# 8051.net
KiCad netlist of a schematic drawn in Altium Designer
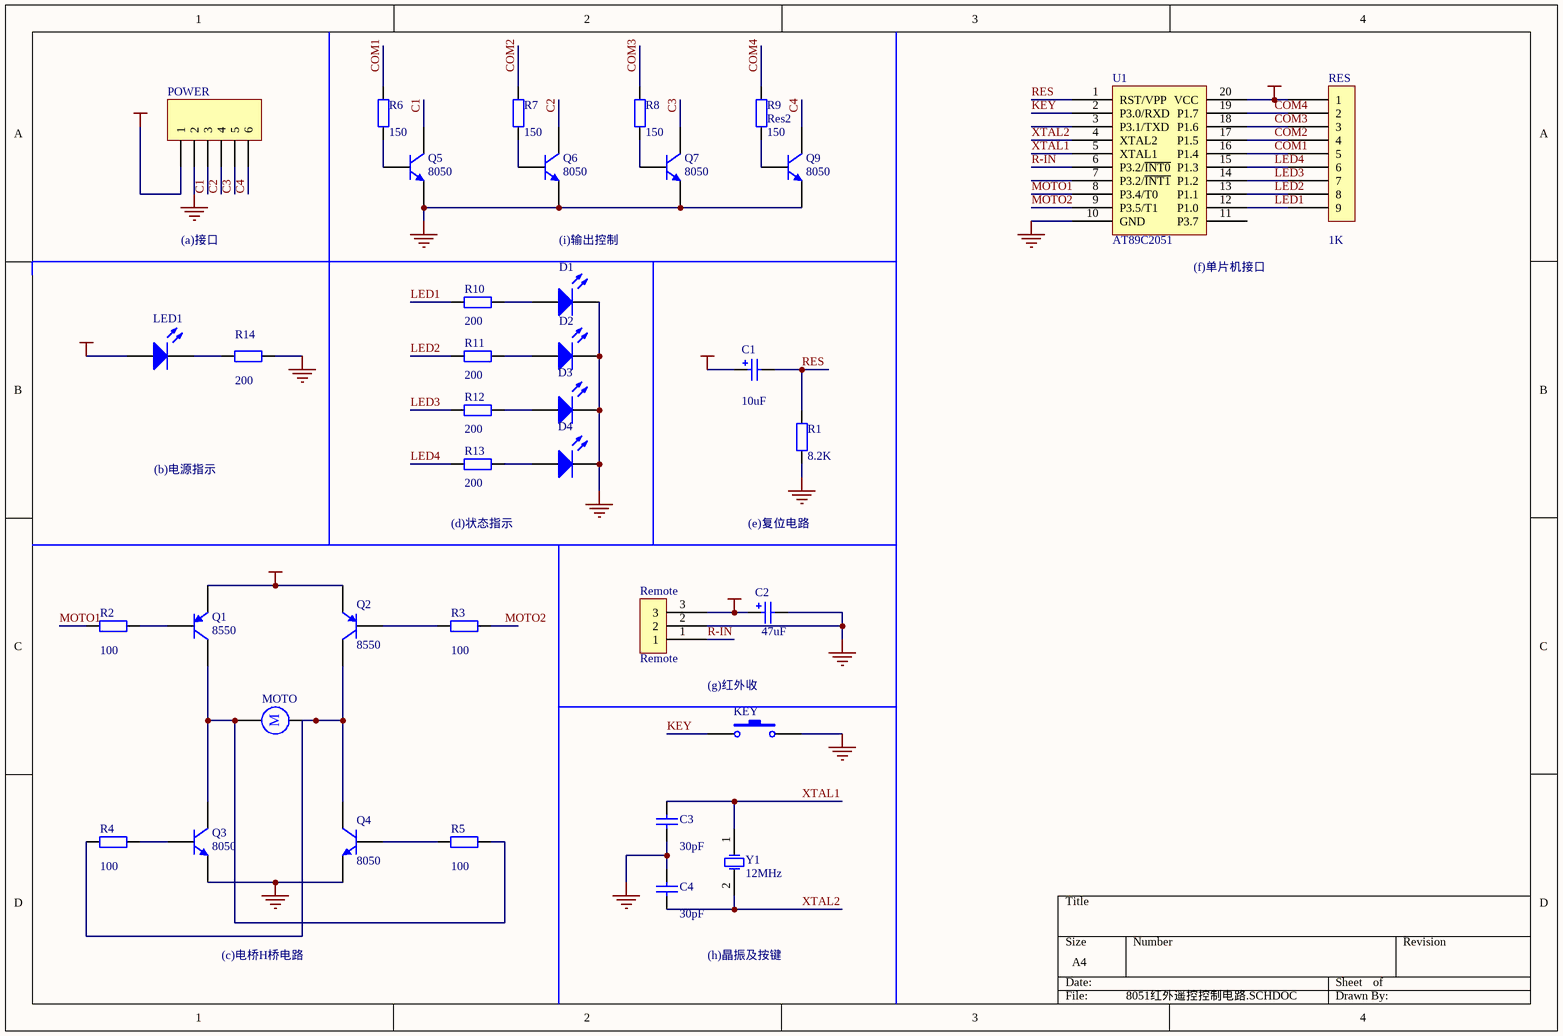
[diagram p0: 8051红外遥控控制电路.SCHDOC]

(export (version "E")
  (design (tool "Eeschema 10.0.6"))
  (components
    (comp (ref "C1")
      (value "10uF")
      (footprint "8051红外遥控控制电路:RB.1/.2")
      (description "Polarized Capacitor (Axial)")
      (fields (field (name "Comment") "Cap Pol2") (field (name "PUBLISHER") "Altium Limited"))
      (libsource (lib "Miscellaneous Devices") (part "Cap Pol2"))
    )
    (comp (ref "C2")
      (value "47uF")
      (footprint "8051红外遥控控制电路:RB.1/.2")
      (description "Polarized Capacitor (Axial)")
      (fields (field (name "Comment") "Cap Pol2") (field (name "PUBLISHER") "Altium Limited"))
      (libsource (lib "Miscellaneous Devices") (part "Cap Pol2"))
    )
    (comp (ref "C3")
      (value "30pF")
      (footprint "RAD-0.1")
      (description "Capacitor")
      (fields (field (name "Comment") "Cap") (field (name "PUBLISHER") "Altium Limited"))
      (libsource (lib "Miscellaneous Devices") (part "Cap"))
    )
    (comp (ref "C4")
      (value "30pF")
      (footprint "RAD-0.1")
      (description "Capacitor")
      (fields (field (name "Comment") "Cap") (field (name "PUBLISHER") "Altium Limited"))
      (libsource (lib "Miscellaneous Devices") (part "Cap"))
    )
    (comp (ref "D1")
      (value "LED2")
      (footprint "8051红外遥控控制电路:LED5")
      (description "Typical RED, GREEN, YELLOW, AMBER GaAs LED")
      (fields (field (name "PUBLISHER") "Altium Limited"))
      (libsource (lib "Miscellaneous Devices") (part "LED2"))
    )
    (comp (ref "D2")
      (value "LED2")
      (footprint "8051红外遥控控制电路:LED5")
      (description "Typical RED, GREEN, YELLOW, AMBER GaAs LED")
      (fields (field (name "PUBLISHER") "Altium Limited"))
      (libsource (lib "Miscellaneous Devices") (part "LED2"))
    )
    (comp (ref "D3")
      (value "LED2")
      (footprint "8051红外遥控控制电路:LED5")
      (description "Typical RED, GREEN, YELLOW, AMBER GaAs LED")
      (fields (field (name "PUBLISHER") "Altium Limited"))
      (libsource (lib "Miscellaneous Devices") (part "LED2"))
    )
    (comp (ref "D4")
      (value "LED2")
      (footprint "8051红外遥控控制电路:LED5")
      (description "Typical RED, GREEN, YELLOW, AMBER GaAs LED")
      (fields (field (name "PUBLISHER") "Altium Limited"))
      (libsource (lib "Miscellaneous Devices") (part "LED2"))
    )
    (comp (ref "KEY")
      (value "SW-PB")
      (footprint "8051红外遥控控制电路:SW_PB")
      (description "Switch")
      (fields (field (name "PUBLISHER") "Altium Limited"))
      (libsource (lib "Miscellaneous Devices") (part "SW-PB"))
    )
    (comp (ref "LED1")
      (value "LED0")
      (footprint "8051红外遥控控制电路:LED5")
      (description "Typical INFRARED GaAs LED")
      (fields (field (name "PUBLISHER") "Altium Limited"))
      (libsource (lib "Miscellaneous Devices") (part "LED0"))
    )
    (comp (ref "MOTO")
      (value "Motor")
      (footprint "Miscellaneous Devices:AXIAL-0.3")
      (description "Motor, General Kind")
      (fields (field (name "PUBLISHER") "Altium Limited"))
      (libsource (lib "Miscellaneous Devices") (part "Motor"))
    )
    (comp (ref "POWER")
      (value "Header 6")
      (footprint "HDR1X6")
      (description "Header, 6-Pin")
      (fields (field (name "PUBLISHER") "Altium Limited"))
      (libsource (lib "Miscellaneous Connectors") (part "Header 6"))
    )
    (comp (ref "Q1")
      (value "8550")
      (footprint "SO-G3/C2.5")
      (description "PNP Bipolar Transistor")
      (fields (field (name "PUBLISHER") "Altium Limited"))
      (libsource (lib "Miscellaneous Devices") (part "PNP"))
    )
    (comp (ref "Q2")
      (value "8550")
      (footprint "SO-G3/C2.5")
      (description "PNP Bipolar Transistor")
      (fields (field (name "PUBLISHER") "Altium Limited"))
      (libsource (lib "Miscellaneous Devices") (part "PNP"))
    )
    (comp (ref "Q3")
      (value "8050")
      (footprint "BCY-W3")
      (description "NPN Bipolar Transistor")
      (fields (field (name "PUBLISHER") "Altium Limited"))
      (libsource (lib "Miscellaneous Devices") (part "NPN"))
    )
    (comp (ref "Q4")
      (value "8050")
      (footprint "BCY-W3")
      (description "NPN Bipolar Transistor")
      (fields (field (name "PUBLISHER") "Altium Limited"))
      (libsource (lib "Miscellaneous Devices") (part "NPN"))
    )
    (comp (ref "Q5")
      (value "8050")
      (footprint "BCY-W3/E4")
      (description "NPN General Purpose Amplifier")
      (fields (field (name "PUBLISHER") "Altium Limited"))
      (libsource (lib "Miscellaneous Devices") (part "2N3904"))
    )
    (comp (ref "Q6")
      (value "8050")
      (footprint "BCY-W3/E4")
      (description "NPN General Purpose Amplifier")
      (fields (field (name "PUBLISHER") "Altium Limited"))
      (libsource (lib "Miscellaneous Devices") (part "2N3904"))
    )
    (comp (ref "Q7")
      (value "8050")
      (footprint "BCY-W3/E4")
      (description "NPN General Purpose Amplifier")
      (fields (field (name "PUBLISHER") "Altium Limited"))
      (libsource (lib "Miscellaneous Devices") (part "2N3904"))
    )
    (comp (ref "Q9")
      (value "8050")
      (footprint "BCY-W3/E4")
      (description "NPN General Purpose Amplifier")
      (fields (field (name "PUBLISHER") "Altium Limited"))
      (libsource (lib "Miscellaneous Devices") (part "2N3904"))
    )
    (comp (ref "R1")
      (value "8.2K")
      (footprint "AXIAL-0.4")
      (description "Resistor")
      (fields (field (name "Comment") "Res2") (field (name "PUBLISHER") "Altium Limited"))
      (libsource (lib "") (part "Res2_1"))
    )
    (comp (ref "R2")
      (value "100")
      (footprint "AXIAL-0.4")
      (description "Resistor")
      (fields (field (name "Comment") "Res2") (field (name "PUBLISHER") "Altium Limited"))
      (libsource (lib "Miscellaneous Devices") (part "Res2"))
    )
    (comp (ref "R3")
      (value "100")
      (footprint "AXIAL-0.4")
      (description "Resistor")
      (fields (field (name "Comment") "Res2") (field (name "PUBLISHER") "Altium Limited"))
      (libsource (lib "Miscellaneous Devices") (part "Res2"))
    )
    (comp (ref "R4")
      (value "100")
      (footprint "AXIAL-0.4")
      (description "Resistor")
      (fields (field (name "Comment") "Res2") (field (name "PUBLISHER") "Altium Limited"))
      (libsource (lib "Miscellaneous Devices") (part "Res2"))
    )
    (comp (ref "R5")
      (value "100")
      (footprint "AXIAL-0.4")
      (description "Resistor")
      (fields (field (name "Comment") "Res2") (field (name "PUBLISHER") "Altium Limited"))
      (libsource (lib "Miscellaneous Devices") (part "Res2"))
    )
    (comp (ref "R6")
      (value "150")
      (footprint "AXIAL-0.4")
      (description "Resistor")
      (fields (field (name "Comment") "Res2") (field (name "PUBLISHER") "Altium Limited"))
      (libsource (lib "") (part "Res2_1"))
    )
    (comp (ref "R7")
      (value "150")
      (footprint "AXIAL-0.4")
      (description "Resistor")
      (fields (field (name "Comment") "Res2") (field (name "PUBLISHER") "Altium Limited"))
      (libsource (lib "") (part "Res2_1"))
    )
    (comp (ref "R8")
      (value "150")
      (footprint "AXIAL-0.4")
      (description "Resistor")
      (fields (field (name "Comment") "Res2") (field (name "PUBLISHER") "Altium Limited"))
      (libsource (lib "") (part "Res2_1"))
    )
    (comp (ref "R9")
      (value "Res2")
      (footprint "AXIAL-0.4")
      (description "Resistor")
      (fields (field (name "ALTIUM_VALUE") "150") (field (name "PUBLISHER") "Altium Limited"))
      (libsource (lib "") (part "Res2_1"))
    )
    (comp (ref "R10")
      (value "200")
      (footprint "AXIAL-0.4")
      (description "Resistor")
      (fields (field (name "Comment") "Res2") (field (name "PUBLISHER") "Altium Limited"))
      (libsource (lib "Miscellaneous Devices") (part "Res2"))
    )
    (comp (ref "R11")
      (value "200")
      (footprint "AXIAL-0.4")
      (description "Resistor")
      (fields (field (name "Comment") "Res2") (field (name "PUBLISHER") "Altium Limited"))
      (libsource (lib "Miscellaneous Devices") (part "Res2"))
    )
    (comp (ref "R12")
      (value "200")
      (footprint "AXIAL-0.4")
      (description "Resistor")
      (fields (field (name "Comment") "Res2") (field (name "PUBLISHER") "Altium Limited"))
      (libsource (lib "Miscellaneous Devices") (part "Res2"))
    )
    (comp (ref "R13")
      (value "200")
      (footprint "AXIAL-0.4")
      (description "Resistor")
      (fields (field (name "Comment") "Res2") (field (name "PUBLISHER") "Altium Limited"))
      (libsource (lib "Miscellaneous Devices") (part "Res2"))
    )
    (comp (ref "R14")
      (value "200")
      (footprint "AXIAL-0.4")
      (description "Resistor")
      (fields (field (name "Comment") "Res2") (field (name "PUBLISHER") "Altium Limited"))
      (libsource (lib "Miscellaneous Devices") (part "Res2"))
    )
    (comp (ref "Remote")
      (value "Remote")
      (footprint "8051红外遥控控制电路:REM")
      (libsource (lib "8051红外遥控控制电路") (part "Remote"))
    )
    (comp (ref "RES")
      (value "1K")
      (footprint "IR Discrete MOSFET:SIP9")
      (fields (field (name "Comment") "RES"))
      (libsource (lib "8051红外遥控控制电路") (part "RES"))
    )
    (comp (ref "U1")
      (value "AT89C2051")
      (footprint "Dallas Communication CEPT T1 Interface:DIP20")
      (libsource (lib "8051红外遥控控制电路") (part "AT89C2051"))
    )
    (comp (ref "Y1")
      (value "12MHz")
      (footprint "BCY-W2/D3.1")
      (description "Crystal Oscillator")
      (fields (field (name "PUBLISHER") "Altium Limited"))
      (libsource (lib "Miscellaneous Devices") (part "XTAL"))
    )
  )
  (nets
    (net (code "1") (name "/C1") (class "Default")
      (node (ref "POWER") (pin "3") (pinfunction "3_3") (pintype "passive"))
      (node (ref "Q5") (pin "3") (pinfunction "C_3") (pintype "passive"))
    )
    (net (code "2") (name "/C2") (class "Default")
      (node (ref "POWER") (pin "4") (pinfunction "4_4") (pintype "passive"))
      (node (ref "Q6") (pin "3") (pinfunction "C_3") (pintype "passive"))
    )
    (net (code "3") (name "/C3") (class "Default")
      (node (ref "POWER") (pin "5") (pinfunction "5_5") (pintype "passive"))
      (node (ref "Q7") (pin "3") (pinfunction "C_3") (pintype "passive"))
    )
    (net (code "4") (name "/C4") (class "Default")
      (node (ref "POWER") (pin "6") (pinfunction "6_6") (pintype "passive"))
      (node (ref "Q9") (pin "3") (pinfunction "C_3") (pintype "passive"))
    )
    (net (code "5") (name "/COM1") (class "Default")
      (node (ref "R6") (pin "2") (pinfunction "2_2") (pintype "passive"))
      (node (ref "RES") (pin "5") (pinfunction "5_5") (pintype "passive"))
      (node (ref "U1") (pin "16") (pinfunction "P1.4_16") (pintype "passive"))
    )
    (net (code "6") (name "/COM2") (class "Default")
      (node (ref "R7") (pin "2") (pinfunction "2_2") (pintype "passive"))
      (node (ref "RES") (pin "4") (pinfunction "4_4") (pintype "passive"))
      (node (ref "U1") (pin "17") (pinfunction "P1.5_17") (pintype "passive"))
    )
    (net (code "7") (name "/COM3") (class "Default")
      (node (ref "R8") (pin "2") (pinfunction "2_2") (pintype "passive"))
      (node (ref "RES") (pin "3") (pinfunction "3_3") (pintype "passive"))
      (node (ref "U1") (pin "18") (pinfunction "P1.6_18") (pintype "passive"))
    )
    (net (code "8") (name "/COM4") (class "Default")
      (node (ref "R9") (pin "2") (pinfunction "2_2") (pintype "passive"))
      (node (ref "RES") (pin "2") (pinfunction "2_2") (pintype "passive"))
      (node (ref "U1") (pin "19") (pinfunction "P1.7_19") (pintype "passive"))
    )
    (net (code "9") (name "/KEY") (class "Default")
      (node (ref "KEY") (pin "1") (pinfunction "1_1") (pintype "passive"))
      (node (ref "U1") (pin "2") (pinfunction "P3.0/RXD_2") (pintype "passive"))
    )
    (net (code "10") (name "/LED1") (class "Default")
      (node (ref "R10") (pin "1") (pinfunction "1_1") (pintype "passive"))
      (node (ref "RES") (pin "9") (pinfunction "9_9") (pintype "passive"))
      (node (ref "U1") (pin "12") (pinfunction "P1.0_12") (pintype "passive"))
    )
    (net (code "11") (name "/LED2") (class "Default")
      (node (ref "R11") (pin "1") (pinfunction "1_1") (pintype "passive"))
      (node (ref "RES") (pin "8") (pinfunction "8_8") (pintype "passive"))
      (node (ref "U1") (pin "13") (pinfunction "P1.1_13") (pintype "passive"))
    )
    (net (code "12") (name "/LED3") (class "Default")
      (node (ref "R12") (pin "1") (pinfunction "1_1") (pintype "passive"))
      (node (ref "RES") (pin "7") (pinfunction "7_7") (pintype "passive"))
      (node (ref "U1") (pin "14") (pinfunction "P1.2_14") (pintype "passive"))
    )
    (net (code "13") (name "/LED4") (class "Default")
      (node (ref "R13") (pin "1") (pinfunction "1_1") (pintype "passive"))
      (node (ref "RES") (pin "6") (pinfunction "6_6") (pintype "passive"))
      (node (ref "U1") (pin "15") (pinfunction "P1.3_15") (pintype "passive"))
    )
    (net (code "14") (name "/MOTO1") (class "Default")
      (node (ref "R2") (pin "1") (pinfunction "1_1") (pintype "passive"))
      (node (ref "U1") (pin "8") (pinfunction "P3.4/T0_8") (pintype "passive"))
    )
    (net (code "15") (name "/MOTO2") (class "Default")
      (node (ref "R3") (pin "2") (pinfunction "2_2") (pintype "passive"))
      (node (ref "U1") (pin "9") (pinfunction "P3.5/T1_9") (pintype "passive"))
    )
    (net (code "16") (name "/R-IN") (class "Default")
      (node (ref "Remote") (pin "1") (pinfunction "1_1") (pintype "passive"))
      (node (ref "U1") (pin "6") (pinfunction "P3.2/~{INT0}_6") (pintype "passive"))
    )
    (net (code "17") (name "/RES") (class "Default")
      (node (ref "C1") (pin "2") (pinfunction "2_2") (pintype "passive"))
      (node (ref "R1") (pin "2") (pinfunction "2_2") (pintype "passive"))
      (node (ref "U1") (pin "1") (pinfunction "RST/VPP_1") (pintype "passive"))
    )
    (net (code "18") (name "/XTAL1") (class "Default")
      (node (ref "C3") (pin "2") (pinfunction "2_2") (pintype "passive"))
      (node (ref "U1") (pin "5") (pinfunction "XTAL1_5") (pintype "passive"))
      (node (ref "Y1") (pin "1") (pinfunction "OSC1_1") (pintype "passive"))
    )
    (net (code "19") (name "/XTAL2") (class "Default")
      (node (ref "C4") (pin "1") (pinfunction "1_1") (pintype "passive"))
      (node (ref "U1") (pin "4") (pinfunction "XTAL2_4") (pintype "passive"))
      (node (ref "Y1") (pin "2") (pinfunction "OSC2_2") (pintype "passive"))
    )
    (net (code "20") (name "GND") (class "Default")
      (node (ref "C2") (pin "2") (pinfunction "2_2") (pintype "passive"))
      (node (ref "C3") (pin "1") (pinfunction "1_1") (pintype "passive"))
      (node (ref "C4") (pin "2") (pinfunction "2_2") (pintype "passive"))
      (node (ref "D1") (pin "2") (pinfunction "K_2") (pintype "passive"))
      (node (ref "D2") (pin "2") (pinfunction "K_2") (pintype "passive"))
      (node (ref "D3") (pin "2") (pinfunction "K_2") (pintype "passive"))
      (node (ref "D4") (pin "2") (pinfunction "K_2") (pintype "passive"))
      (node (ref "KEY") (pin "2") (pinfunction "2_2") (pintype "passive"))
      (node (ref "POWER") (pin "2") (pinfunction "2_2") (pintype "passive"))
      (node (ref "Q3") (pin "3") (pinfunction "E_3") (pintype "passive"))
      (node (ref "Q4") (pin "3") (pinfunction "E_3") (pintype "passive"))
      (node (ref "Q5") (pin "1") (pinfunction "E_1") (pintype "passive"))
      (node (ref "Q6") (pin "1") (pinfunction "E_1") (pintype "passive"))
      (node (ref "Q7") (pin "1") (pinfunction "E_1") (pintype "passive"))
      (node (ref "Q9") (pin "1") (pinfunction "E_1") (pintype "passive"))
      (node (ref "R1") (pin "1") (pinfunction "1_1") (pintype "passive"))
      (node (ref "R14") (pin "2") (pinfunction "2_2") (pintype "passive"))
      (node (ref "Remote") (pin "2") (pinfunction "2_2") (pintype "passive"))
      (node (ref "U1") (pin "10") (pinfunction "GND_10") (pintype "passive"))
    )
    (net (code "21") (name "Net-(D1-A)") (class "Default")
      (node (ref "D1") (pin "1") (pinfunction "A_1") (pintype "passive"))
      (node (ref "R10") (pin "2") (pinfunction "2_2") (pintype "passive"))
    )
    (net (code "22") (name "Net-(D2-A)") (class "Default")
      (node (ref "D2") (pin "1") (pinfunction "A_1") (pintype "passive"))
      (node (ref "R11") (pin "2") (pinfunction "2_2") (pintype "passive"))
    )
    (net (code "23") (name "Net-(D3-A)") (class "Default")
      (node (ref "D3") (pin "1") (pinfunction "A_1") (pintype "passive"))
      (node (ref "R12") (pin "2") (pinfunction "2_2") (pintype "passive"))
    )
    (net (code "24") (name "Net-(D4-A)") (class "Default")
      (node (ref "D4") (pin "1") (pinfunction "A_1") (pintype "passive"))
      (node (ref "R13") (pin "2") (pinfunction "2_2") (pintype "passive"))
    )
    (net (code "25") (name "Net-(LED1-K)") (class "Default")
      (node (ref "LED1") (pin "2") (pinfunction "K_2") (pintype "passive"))
      (node (ref "R14") (pin "1") (pinfunction "1_1") (pintype "passive"))
    )
    (net (code "26") (name "Net-(Q1-B)") (class "Default")
      (node (ref "Q1") (pin "2") (pinfunction "B_2") (pintype "passive"))
      (node (ref "R2") (pin "2") (pinfunction "2_2") (pintype "passive"))
    )
    (net (code "27") (name "Net-(Q1-C)") (class "Default")
      (node (ref "MOTO") (pin "1") (pinfunction "1_1") (pintype "passive"))
      (node (ref "Q1") (pin "1") (pinfunction "C_1") (pintype "passive"))
      (node (ref "Q3") (pin "1") (pinfunction "C_1") (pintype "passive"))
      (node (ref "R5") (pin "2") (pinfunction "2_2") (pintype "passive"))
    )
    (net (code "28") (name "Net-(Q2-B)") (class "Default")
      (node (ref "Q2") (pin "2") (pinfunction "B_2") (pintype "passive"))
      (node (ref "R3") (pin "1") (pinfunction "1_1") (pintype "passive"))
    )
    (net (code "29") (name "Net-(Q2-C)") (class "Default")
      (node (ref "MOTO") (pin "2") (pinfunction "2_2") (pintype "passive"))
      (node (ref "Q2") (pin "1") (pinfunction "C_1") (pintype "passive"))
      (node (ref "Q4") (pin "1") (pinfunction "C_1") (pintype "passive"))
      (node (ref "R4") (pin "1") (pinfunction "1_1") (pintype "passive"))
    )
    (net (code "30") (name "Net-(Q3-B)") (class "Default")
      (node (ref "Q3") (pin "2") (pinfunction "B_2") (pintype "passive"))
      (node (ref "R4") (pin "2") (pinfunction "2_2") (pintype "passive"))
    )
    (net (code "31") (name "Net-(Q4-B)") (class "Default")
      (node (ref "Q4") (pin "2") (pinfunction "B_2") (pintype "passive"))
      (node (ref "R5") (pin "1") (pinfunction "1_1") (pintype "passive"))
    )
    (net (code "32") (name "Net-(Q5-B)") (class "Default")
      (node (ref "Q5") (pin "2") (pinfunction "B_2") (pintype "passive"))
      (node (ref "R6") (pin "1") (pinfunction "1_1") (pintype "passive"))
    )
    (net (code "33") (name "Net-(Q6-B)") (class "Default")
      (node (ref "Q6") (pin "2") (pinfunction "B_2") (pintype "passive"))
      (node (ref "R7") (pin "1") (pinfunction "1_1") (pintype "passive"))
    )
    (net (code "34") (name "Net-(Q7-B)") (class "Default")
      (node (ref "Q7") (pin "2") (pinfunction "B_2") (pintype "passive"))
      (node (ref "R8") (pin "1") (pinfunction "1_1") (pintype "passive"))
    )
    (net (code "35") (name "Net-(Q9-B)") (class "Default")
      (node (ref "Q9") (pin "2") (pinfunction "B_2") (pintype "passive"))
      (node (ref "R9") (pin "1") (pinfunction "1_1") (pintype "passive"))
    )
    (net (code "36") (name "VCC") (class "Default")
      (node (ref "C1") (pin "1") (pinfunction "1_1") (pintype "passive"))
      (node (ref "C2") (pin "1") (pinfunction "1_1") (pintype "passive"))
      (node (ref "LED1") (pin "1") (pinfunction "A_1") (pintype "passive"))
      (node (ref "POWER") (pin "1") (pinfunction "1_1") (pintype "passive"))
      (node (ref "Q1") (pin "3") (pinfunction "E_3") (pintype "passive"))
      (node (ref "Q2") (pin "3") (pinfunction "E_3") (pintype "passive"))
      (node (ref "RES") (pin "1") (pinfunction "1_1") (pintype "passive"))
      (node (ref "Remote") (pin "3") (pinfunction "3_3") (pintype "passive"))
      (node (ref "U1") (pin "20") (pinfunction "VCC_20") (pintype "passive"))
    )
    (net (code "37") (name "unconnected-(U1-P3.1{slash}TXD-Pad3)") (class "Default")
      (node (ref "U1") (pin "3") (pinfunction "P3.1/TXD_3") (pintype "passive"))
    )
    (net (code "38") (name "unconnected-(U1-P3.2{slash}~{INT1}-Pad7)") (class "Default")
      (node (ref "U1") (pin "7") (pinfunction "P3.2/~{INT1}_7") (pintype "passive"))
    )
    (net (code "39") (name "unconnected-(U1-P3.7-Pad11)") (class "Default")
      (node (ref "U1") (pin "11") (pinfunction "P3.7_11") (pintype "passive"))
    )
  )
)
